# GPS_TRACKER_MINI.net
KiCad netlist of a schematic drawn in EAGLE
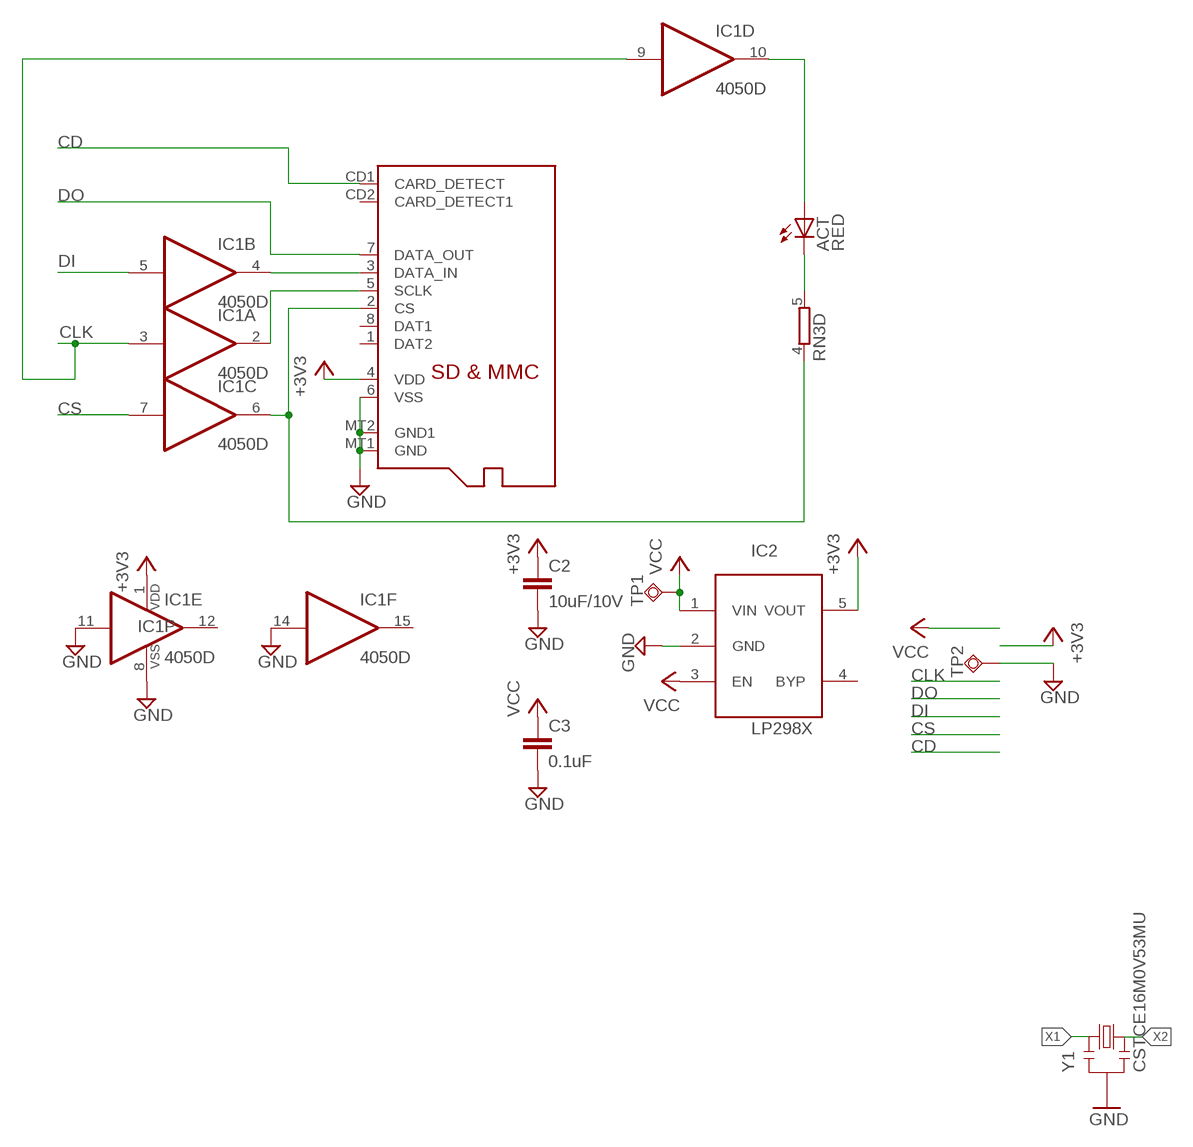
[diagram p0: schematic, sheet 1, part 1 of 2]
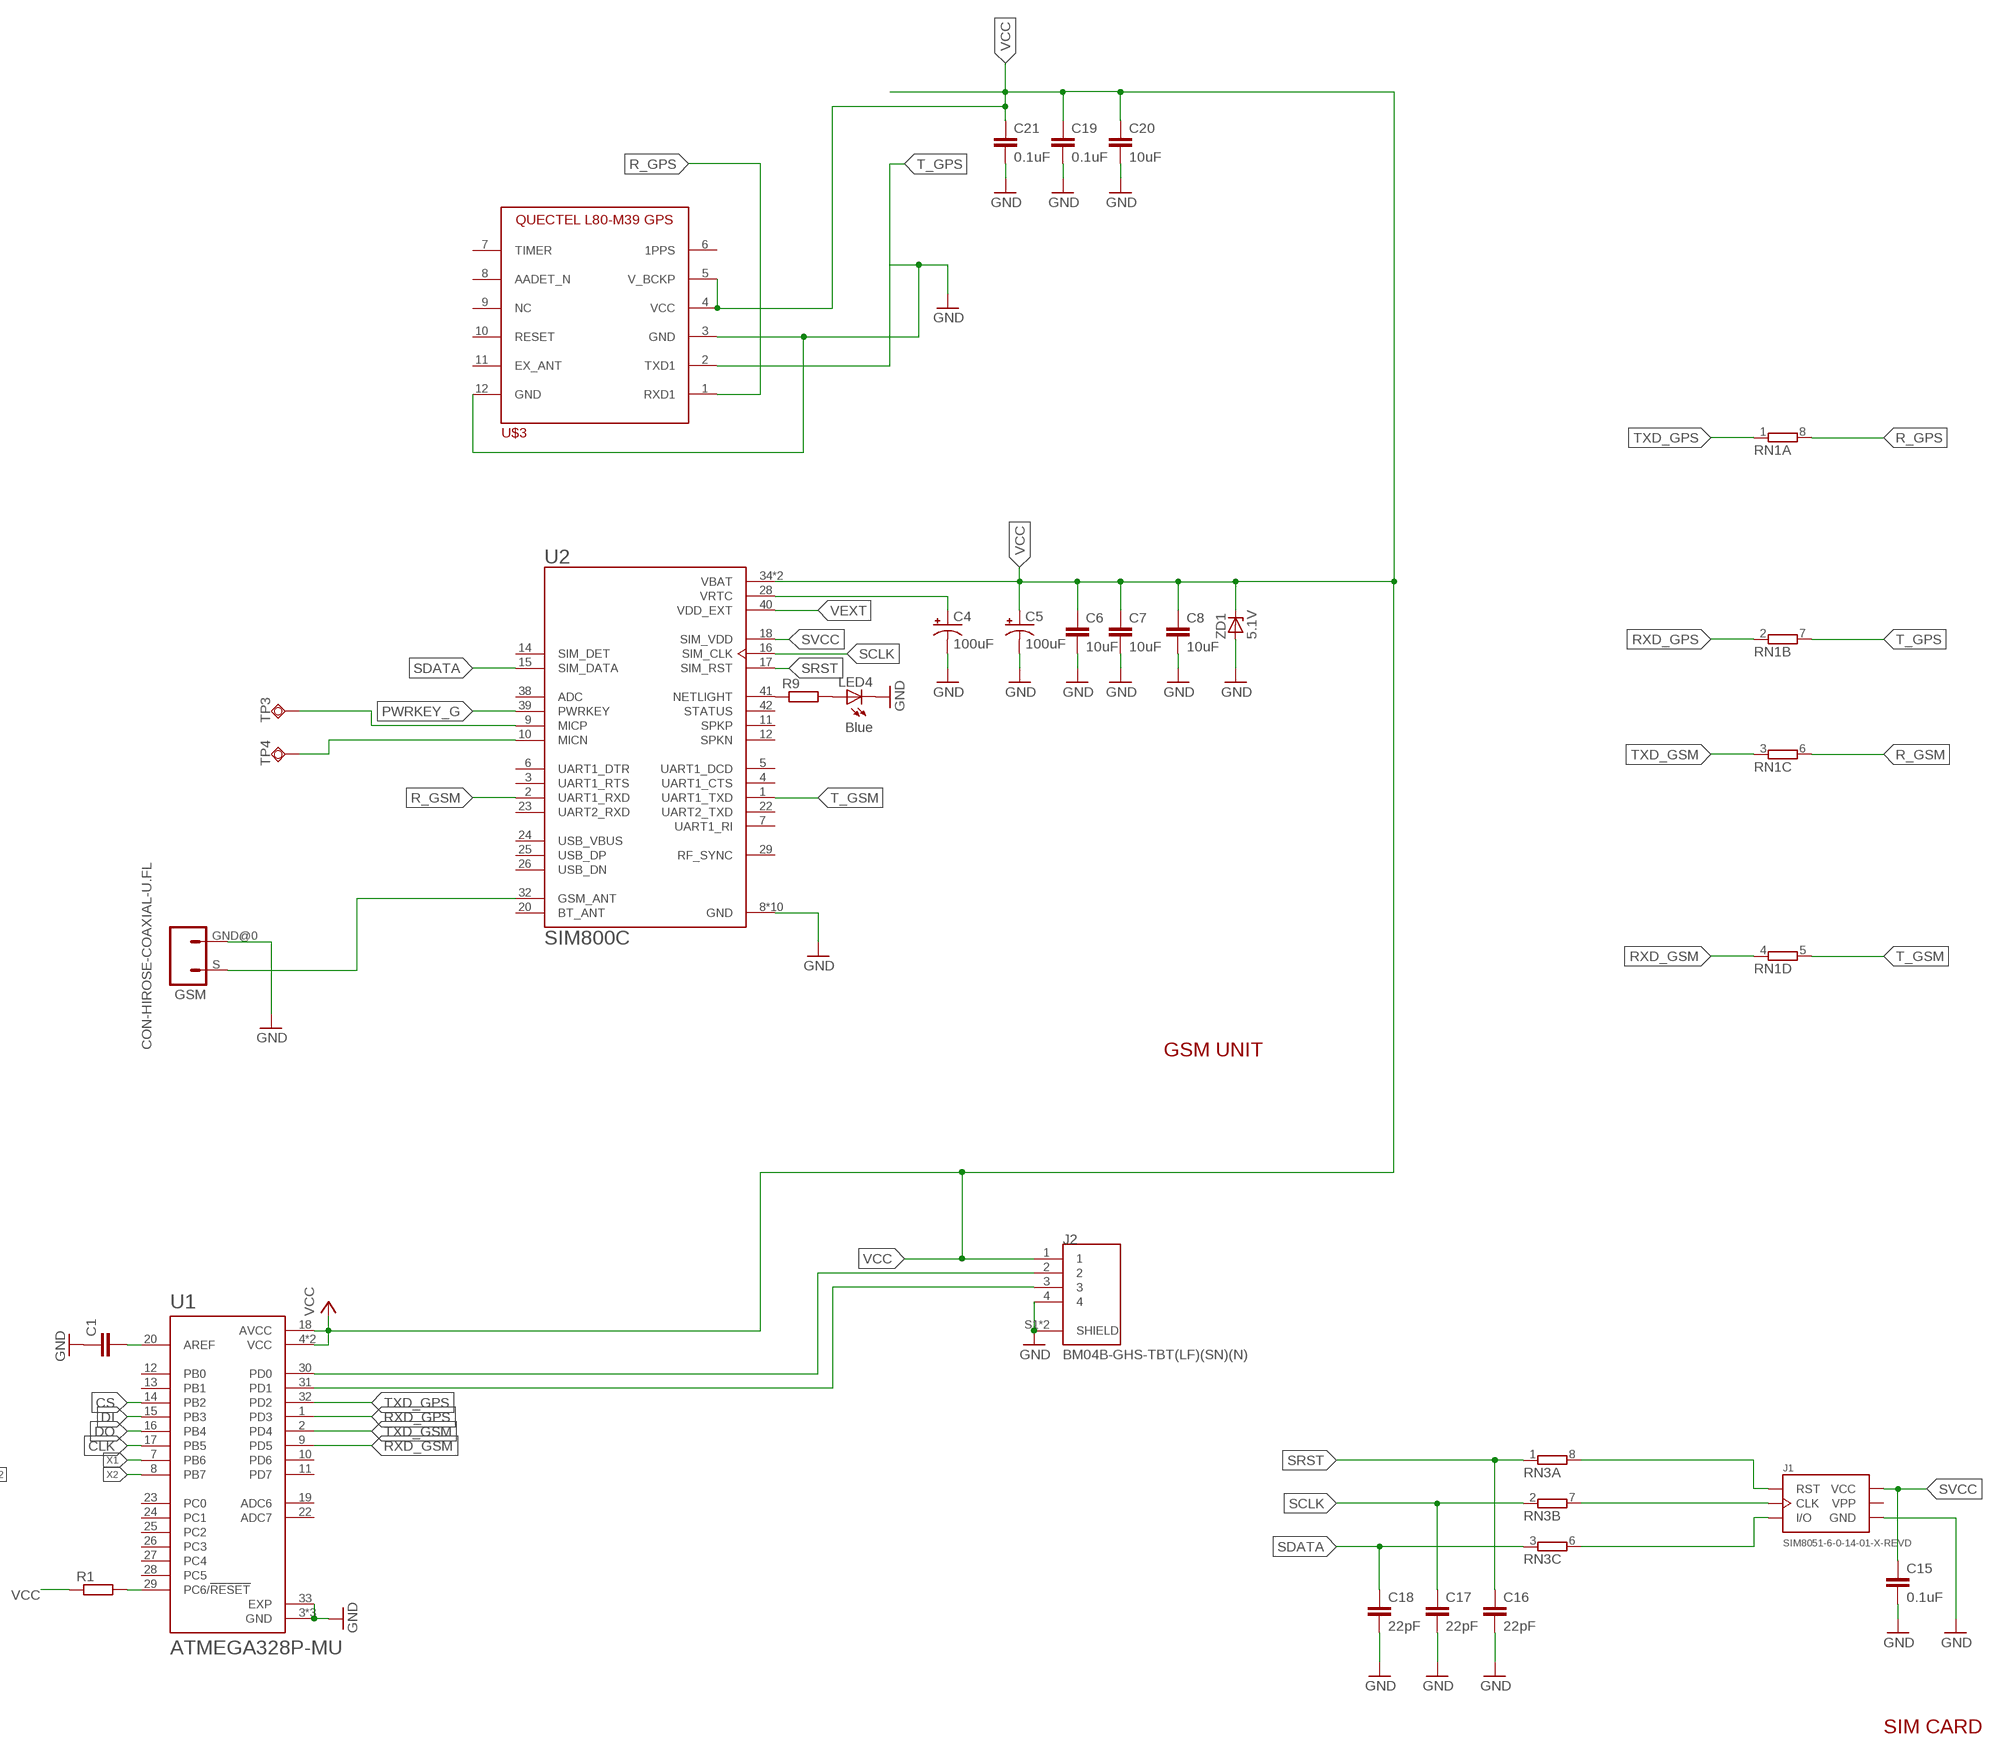
[diagram p1: schematic, sheet 1, part 2 of 2]

(export (version "E")
  (design (tool "Eeschema 10.0.6"))
  (components
    (comp (ref "ACT")
      (value "RED")
      (footprint "eagle-import:CHIP-LED0805")
      (libsource (lib "eagle-import") (part "LEDCHIP-LED0805"))
    )
    (comp (ref "C1")
      (value "C-EUC0603K")
      (footprint "eagle-import:C0603K")
      (libsource (lib "eagle-import") (part "C-EUC0603K"))
    )
    (comp (ref "C2")
      (value "10uF/10V")
      (footprint "eagle-import:C0603")
      (libsource (lib "eagle-import") (part "C-EUC0603"))
    )
    (comp (ref "C3")
      (value "0.1uF")
      (footprint "eagle-import:C0603")
      (libsource (lib "eagle-import") (part "C-EUC0603"))
    )
    (comp (ref "C4")
      (value "100uF")
      (footprint "eagle-import:B_3528-21R")
      (libsource (lib "eagle-import") (part "CPOL-USB/3528-21R"))
    )
    (comp (ref "C5")
      (value "100uF")
      (footprint "eagle-import:B_3528-21R")
      (libsource (lib "eagle-import") (part "CPOL-USB/3528-21R"))
    )
    (comp (ref "C6")
      (value "10uF")
      (footprint "eagle-import:C0603")
      (libsource (lib "eagle-import") (part "C-EUC0603"))
    )
    (comp (ref "C7")
      (value "10uF")
      (footprint "eagle-import:C0603")
      (libsource (lib "eagle-import") (part "C-EUC0603"))
    )
    (comp (ref "C8")
      (value "10uF")
      (footprint "eagle-import:C0603")
      (libsource (lib "eagle-import") (part "C-EUC0603"))
    )
    (comp (ref "C15")
      (value "0.1uF")
      (footprint "eagle-import:C0603")
      (libsource (lib "eagle-import") (part "C-EUC0603"))
    )
    (comp (ref "C16")
      (value "22pF")
      (footprint "eagle-import:C0603")
      (libsource (lib "eagle-import") (part "C-EUC0603"))
    )
    (comp (ref "C17")
      (value "22pF")
      (footprint "eagle-import:C0603")
      (libsource (lib "eagle-import") (part "C-EUC0603"))
    )
    (comp (ref "C18")
      (value "22pF")
      (footprint "eagle-import:C0603")
      (libsource (lib "eagle-import") (part "C-EUC0603"))
    )
    (comp (ref "C19")
      (value "0.1uF")
      (footprint "eagle-import:C0603")
      (libsource (lib "eagle-import") (part "C-EUC0603"))
    )
    (comp (ref "C20")
      (value "10uF")
      (footprint "eagle-import:C0603")
      (libsource (lib "eagle-import") (part "C-EUC0603"))
    )
    (comp (ref "C21")
      (value "0.1uF")
      (footprint "eagle-import:C0603")
      (libsource (lib "eagle-import") (part "C-EUC0603"))
    )
    (comp (ref "GSM")
      (value "CON-HIROSE-COAXIAL-U.FL")
      (footprint "eagle-import:CON-U.FL")
      (libsource (lib "eagle-import") (part "CON-HIROSE-COAXIAL-U.FL"))
    )
    (comp (ref "IC1")
      (value "4050D")
      (footprint "eagle-import:SO16")
      (libsource (lib "eagle-import") (part "4050D"))
    )
    (comp (ref "IC2")
      (value "LP298XS")
      (footprint "eagle-import:SOT23-5L")
      (libsource (lib "eagle-import") (part "LP298XS"))
    )
    (comp (ref "J1")
      (value "SIM8051-6-0-14-01-X-REVD")
      (footprint "eagle-import:GCT_SIM8051-6-0-14-01-X-REVD")
      (fields (field (name "MF") "Global Connector Technology") (field (name "MP") "SIM8051-6-0-14-01-A"))
      (libsource (lib "eagle-import") (part "SIM8051-6-0-14-01-X-REVD"))
    )
    (comp (ref "J2")
      (value "BM04B-GHS-TBT(LF)(SN)(N)")
      (footprint "eagle-import:JST_BM04B-GHS-TBT(LF)(SN)(N)")
      (fields (field (name "MF") "JST Sales"))
      (libsource (lib "eagle-import") (part "BM04B-GHS-TBT(LF)(SN)(N)"))
    )
    (comp (ref "LED4")
      (value "Blue")
      (footprint "eagle-import:CHIP-LED0805")
      (libsource (lib "eagle-import") (part "LEDCHIP-LED0805"))
    )
    (comp (ref "R1")
      (value "R-EU_R0603")
      (footprint "eagle-import:R0603")
      (libsource (lib "eagle-import") (part "R-EU_R0603"))
    )
    (comp (ref "R9")
      (value "R-EU_R0603")
      (footprint "eagle-import:R0603")
      (libsource (lib "eagle-import") (part "R-EU_R0603"))
    )
    (comp (ref "RN1")
      (value "4R-N0603-ARC")
      (footprint "eagle-import:0603-ARC")
      (libsource (lib "eagle-import") (part "4R-N0603-ARC"))
    )
    (comp (ref "RN3")
      (value "4R-N0603-ARC")
      (footprint "eagle-import:0603-ARC")
      (libsource (lib "eagle-import") (part "4R-N0603-ARC"))
    )
    (comp (ref "TP1")
      (value "TPSQTP20R")
      (footprint "eagle-import:TP20R")
      (libsource (lib "eagle-import") (part "TPSQTP20R"))
    )
    (comp (ref "TP2")
      (value "TPSQTP20R")
      (footprint "eagle-import:TP20R")
      (libsource (lib "eagle-import") (part "TPSQTP20R"))
    )
    (comp (ref "TP3")
      (value "TPSQTP14R")
      (footprint "eagle-import:TP14R")
      (libsource (lib "eagle-import") (part "TPSQTP14R"))
    )
    (comp (ref "TP4")
      (value "TPSQTP14R")
      (footprint "eagle-import:TP14R")
      (libsource (lib "eagle-import") (part "TPSQTP14R"))
    )
    (comp (ref "U$3")
      (value "L80_GNSS_MODULE")
      (footprint "eagle-import:L80_PACKAGE")
      (libsource (lib "eagle-import") (part "L80_GNSS_MODULE"))
    )
    (comp (ref "U1")
      (value "ATMEGA328P-MU")
      (footprint "eagle-import:QFN50P500X500X100-33N")
      (fields (field (name "MF") "Microchip"))
      (libsource (lib "eagle-import") (part "ATMEGA328P-MU"))
    )
    (comp (ref "U2")
      (value "SIM800C")
      (footprint "eagle-import:LCC110P1570X1760X250-42N")
      (fields (field (name "MF") "Simcom"))
      (libsource (lib "eagle-import") (part "SIM800C"))
    )
    (comp (ref "X1")
      (value "MICROSD")
      (footprint "eagle-import:MICROSD")
      (libsource (lib "eagle-import") (part "MICROSD"))
    )
    (comp (ref "Y1")
      (value "CSTCE16M0V53MU")
      (footprint "eagle-import:CSTCE16M0V53")
      (fields (field (name "MF") "Murata Electronics") (field (name "MP") "CSTCE16M0V53"))
      (libsource (lib "eagle-import") (part "CSTCE16M0V53MU"))
    )
    (comp (ref "ZD1")
      (value "5.1V")
      (footprint "eagle-import:SOD123")
      (libsource (lib "eagle-import") (part "ZD-SOD123"))
    )
  )
  (nets
    (net (code "1") (name "+3V3") (class "Default")
      (node (ref "C2") (pin "1") (pinfunction "1_1") (pintype "passive"))
      (node (ref "IC1") (pin "1") (pinfunction "VDD_1") (pintype "power_in"))
      (node (ref "IC2") (pin "5") (pinfunction "VOUT_5") (pintype "bidirectional"))
      (node (ref "X1") (pin "4") (pinfunction "VDD_4") (pintype "power_in"))
    )
    (net (code "2") (name "/CD") (class "Default")
      (node (ref "X1") (pin "CD1") (pinfunction "CARD_DETECT_CD1") (pintype "passive"))
    )
    (net (code "3") (name "/VPP") (class "Default")
      (node (ref "J1") (pin "C6") (pinfunction "VPP_C6") (pintype "power_in"))
    )
    (net (code "4") (name "CLK") (class "Default")
      (node (ref "IC1") (pin "3") (pinfunction "I_3") (pintype "input"))
      (node (ref "IC1") (pin "9") (pinfunction "I_9") (pintype "input"))
      (node (ref "U1") (pin "17") (pinfunction "PB5_17") (pintype "bidirectional"))
    )
    (net (code "5") (name "CS") (class "Default")
      (node (ref "IC1") (pin "7") (pinfunction "I_7") (pintype "input"))
      (node (ref "U1") (pin "14") (pinfunction "PB2_14") (pintype "bidirectional"))
    )
    (net (code "6") (name "DI") (class "Default")
      (node (ref "IC1") (pin "5") (pinfunction "I_5") (pintype "input"))
      (node (ref "U1") (pin "15") (pinfunction "PB3_15") (pintype "bidirectional"))
    )
    (net (code "7") (name "DO") (class "Default")
      (node (ref "U1") (pin "16") (pinfunction "PB4_16") (pintype "bidirectional"))
      (node (ref "X1") (pin "7") (pinfunction "DATA_OUT_7") (pintype "output"))
    )
    (net (code "8") (name "GND") (class "Default")
      (node (ref "C1") (pin "1") (pinfunction "1_1") (pintype "passive"))
      (node (ref "C15") (pin "2") (pinfunction "2_2") (pintype "passive"))
      (node (ref "C16") (pin "2") (pinfunction "2_2") (pintype "passive"))
      (node (ref "C17") (pin "2") (pinfunction "2_2") (pintype "passive"))
      (node (ref "C18") (pin "2") (pinfunction "2_2") (pintype "passive"))
      (node (ref "C19") (pin "2") (pinfunction "2_2") (pintype "passive"))
      (node (ref "C2") (pin "2") (pinfunction "2_2") (pintype "passive"))
      (node (ref "C20") (pin "2") (pinfunction "2_2") (pintype "passive"))
      (node (ref "C21") (pin "2") (pinfunction "2_2") (pintype "passive"))
      (node (ref "C3") (pin "2") (pinfunction "2_2") (pintype "passive"))
      (node (ref "C4") (pin "-") (pinfunction "-_-") (pintype "passive"))
      (node (ref "C5") (pin "-") (pinfunction "-_-") (pintype "passive"))
      (node (ref "C6") (pin "2") (pinfunction "2_2") (pintype "passive"))
      (node (ref "C7") (pin "2") (pinfunction "2_2") (pintype "passive"))
      (node (ref "C8") (pin "2") (pinfunction "2_2") (pintype "passive"))
      (node (ref "GSM") (pin "GND@0") (pinfunction "2_GND@0") (pintype "passive"))
      (node (ref "IC1") (pin "11") (pinfunction "I_11") (pintype "input"))
      (node (ref "IC1") (pin "14") (pinfunction "I_14") (pintype "input"))
      (node (ref "IC1") (pin "8") (pinfunction "VSS_8") (pintype "power_in"))
      (node (ref "IC2") (pin "2") (pinfunction "GND_2") (pintype "bidirectional"))
      (node (ref "J1") (pin "C5") (pinfunction "GND_C5") (pintype "power_in"))
      (node (ref "J2") (pin "4") (pinfunction "4_4") (pintype "passive"))
      (node (ref "J2") (pin "S1") (pinfunction "SHIELD_S1") (pintype "passive"))
      (node (ref "J2") (pin "S2") (pinfunction "SHIELD_S2") (pintype "passive"))
      (node (ref "LED4") (pin "C") (pinfunction "C_C") (pintype "passive"))
      (node (ref "TP2") (pin "TP") (pinfunction "TP_TP") (pintype "input"))
      (node (ref "U$3") (pin "12") (pinfunction "GND_12") (pintype "bidirectional"))
      (node (ref "U$3") (pin "3") (pinfunction "GND_3") (pintype "bidirectional"))
      (node (ref "U1") (pin "21") (pinfunction "GND_21") (pintype "power_in"))
      (node (ref "U1") (pin "3") (pinfunction "GND_3") (pintype "power_in"))
      (node (ref "U1") (pin "33") (pinfunction "EXP_33") (pintype "power_in"))
      (node (ref "U1") (pin "5") (pinfunction "GND_5") (pintype "power_in"))
      (node (ref "U2") (pin "13") (pinfunction "GND_13") (pintype "power_in"))
      (node (ref "U2") (pin "19") (pinfunction "GND_19") (pintype "power_in"))
      (node (ref "U2") (pin "21") (pinfunction "GND_21") (pintype "power_in"))
      (node (ref "U2") (pin "27") (pinfunction "GND_27") (pintype "power_in"))
      (node (ref "U2") (pin "30") (pinfunction "GND_30") (pintype "power_in"))
      (node (ref "U2") (pin "31") (pinfunction "GND_31") (pintype "power_in"))
      (node (ref "U2") (pin "33") (pinfunction "GND_33") (pintype "power_in"))
      (node (ref "U2") (pin "36") (pinfunction "GND_36") (pintype "power_in"))
      (node (ref "U2") (pin "37") (pinfunction "GND_37") (pintype "power_in"))
      (node (ref "U2") (pin "8") (pinfunction "GND_8") (pintype "power_in"))
      (node (ref "X1") (pin "6") (pinfunction "VSS_6") (pintype "power_in"))
      (node (ref "X1") (pin "MT1") (pinfunction "GND_MT1") (pintype "power_in"))
      (node (ref "X1") (pin "MT2") (pinfunction "GND1_MT2") (pintype "power_in"))
      (node (ref "Y1") (pin "2") (pinfunction "2_2") (pintype "passive"))
      (node (ref "ZD1") (pin "A") (pinfunction "A_A") (pintype "passive"))
    )
    (net (code "9") (name "Net-(GSM-1)") (class "Default")
      (node (ref "GSM") (pin "S") (pinfunction "1_S") (pintype "passive"))
      (node (ref "U2") (pin "32") (pinfunction "GSM_ANT_32") (pintype "bidirectional"))
    )
    (net (code "10") (name "Net-(IC1A-O)") (class "Default")
      (node (ref "IC1") (pin "2") (pinfunction "O_2") (pintype "output"))
      (node (ref "X1") (pin "5") (pinfunction "SCLK_5") (pintype "input"))
    )
    (net (code "11") (name "Net-(IC1B-O)") (class "Default")
      (node (ref "IC1") (pin "4") (pinfunction "O_4") (pintype "output"))
      (node (ref "X1") (pin "3") (pinfunction "DATA_IN_3") (pintype "input"))
    )
    (net (code "12") (name "Net-(IC1C-O)") (class "Default")
      (node (ref "IC1") (pin "6") (pinfunction "O_6") (pintype "output"))
      (node (ref "RN3") (pin "4") (pinfunction "1_4") (pintype "passive"))
      (node (ref "X1") (pin "2") (pinfunction "CS_2") (pintype "input"))
    )
    (net (code "13") (name "Net-(IC1D-O)") (class "Default")
      (node (ref "ACT") (pin "A") (pinfunction "A_A") (pintype "passive"))
      (node (ref "IC1") (pin "10") (pinfunction "O_10") (pintype "output"))
    )
    (net (code "14") (name "Net-(J1-CLK)") (class "Default")
      (node (ref "J1") (pin "C3") (pinfunction "CLK_C3") (pintype "input"))
      (node (ref "RN3") (pin "7") (pinfunction "2_7") (pintype "passive"))
    )
    (net (code "15") (name "Net-(J1-I{slash}O)") (class "Default")
      (node (ref "J1") (pin "C7") (pinfunction "I/O_C7") (pintype "bidirectional"))
      (node (ref "RN3") (pin "6") (pinfunction "2_6") (pintype "passive"))
    )
    (net (code "16") (name "Net-(J1-RST)") (class "Default")
      (node (ref "J1") (pin "C2") (pinfunction "RST_C2") (pintype "input"))
      (node (ref "RN3") (pin "8") (pinfunction "2_8") (pintype "passive"))
    )
    (net (code "17") (name "Net-(LED4-PadA)") (class "Default")
      (node (ref "LED4") (pin "A") (pinfunction "A_A") (pintype "passive"))
      (node (ref "R9") (pin "2") (pinfunction "2_2") (pintype "passive"))
    )
    (net (code "18") (name "Net-(RN3D-2)") (class "Default")
      (node (ref "ACT") (pin "C") (pinfunction "C_C") (pintype "passive"))
      (node (ref "RN3") (pin "5") (pinfunction "2_5") (pintype "passive"))
    )
    (net (code "19") (name "Net-(U1-AREF)") (class "Default")
      (node (ref "C1") (pin "2") (pinfunction "2_2") (pintype "passive"))
      (node (ref "U1") (pin "20") (pinfunction "AREF_20") (pintype "input"))
    )
    (net (code "20") (name "Net-(U1-PC6{slash}~{RESET})") (class "Default")
      (node (ref "R1") (pin "2") (pinfunction "2_2") (pintype "passive"))
      (node (ref "U1") (pin "29") (pinfunction "PC6/~{RESET}_29") (pintype "bidirectional"))
    )
    (net (code "21") (name "Net-(U1-PD0)") (class "Default")
      (node (ref "J2") (pin "2") (pinfunction "2_2") (pintype "passive"))
      (node (ref "U1") (pin "30") (pinfunction "PD0_30") (pintype "bidirectional"))
    )
    (net (code "22") (name "Net-(U1-PD1)") (class "Default")
      (node (ref "J2") (pin "3") (pinfunction "3_3") (pintype "passive"))
      (node (ref "U1") (pin "31") (pinfunction "PD1_31") (pintype "bidirectional"))
    )
    (net (code "23") (name "Net-(U2-MICN)") (class "Default")
      (node (ref "TP4") (pin "TP") (pinfunction "TP_TP") (pintype "input"))
      (node (ref "U2") (pin "10") (pinfunction "MICN_10") (pintype "input"))
    )
    (net (code "24") (name "Net-(U2-MICP)") (class "Default")
      (node (ref "TP3") (pin "TP") (pinfunction "TP_TP") (pintype "input"))
      (node (ref "U2") (pin "9") (pinfunction "MICP_9") (pintype "input"))
    )
    (net (code "25") (name "Net-(U2-NETLIGHT)") (class "Default")
      (node (ref "R9") (pin "1") (pinfunction "1_1") (pintype "passive"))
      (node (ref "U2") (pin "41") (pinfunction "NETLIGHT_41") (pintype "output"))
    )
    (net (code "26") (name "Net-(U2-VRTC)") (class "Default")
      (node (ref "C4") (pin "+") (pinfunction "+_+") (pintype "passive"))
      (node (ref "U2") (pin "28") (pinfunction "VRTC_28") (pintype "power_in"))
    )
    (net (code "27") (name "PWRKEY_G") (class "Default")
      (node (ref "U2") (pin "39") (pinfunction "PWRKEY_39") (pintype "input"))
    )
    (net (code "28") (name "RXD_GPS") (class "Default")
      (node (ref "RN1") (pin "2") (pinfunction "1_2") (pintype "passive"))
      (node (ref "U1") (pin "1") (pinfunction "PD3_1") (pintype "bidirectional"))
    )
    (net (code "29") (name "RXD_GSM") (class "Default")
      (node (ref "RN1") (pin "4") (pinfunction "1_4") (pintype "passive"))
      (node (ref "U1") (pin "9") (pinfunction "PD5_9") (pintype "bidirectional"))
    )
    (net (code "30") (name "R_GPS") (class "Default")
      (node (ref "RN1") (pin "8") (pinfunction "2_8") (pintype "passive"))
      (node (ref "U$3") (pin "1") (pinfunction "RXD1_1") (pintype "bidirectional"))
    )
    (net (code "31") (name "R_GSM") (class "Default")
      (node (ref "RN1") (pin "6") (pinfunction "2_6") (pintype "passive"))
      (node (ref "U2") (pin "2") (pinfunction "UART1_RXD_2") (pintype "input"))
    )
    (net (code "32") (name "SCLK") (class "Default")
      (node (ref "C17") (pin "1") (pinfunction "1_1") (pintype "passive"))
      (node (ref "RN3") (pin "2") (pinfunction "1_2") (pintype "passive"))
      (node (ref "U2") (pin "16") (pinfunction "SIM_CLK_16") (pintype "output"))
    )
    (net (code "33") (name "SDATA") (class "Default")
      (node (ref "C18") (pin "1") (pinfunction "1_1") (pintype "passive"))
      (node (ref "RN3") (pin "3") (pinfunction "1_3") (pintype "passive"))
      (node (ref "U2") (pin "15") (pinfunction "SIM_DATA_15") (pintype "bidirectional"))
    )
    (net (code "34") (name "SRST") (class "Default")
      (node (ref "C16") (pin "1") (pinfunction "1_1") (pintype "passive"))
      (node (ref "RN3") (pin "1") (pinfunction "1_1") (pintype "passive"))
      (node (ref "U2") (pin "17") (pinfunction "SIM_RST_17") (pintype "output"))
    )
    (net (code "35") (name "SVCC") (class "Default")
      (node (ref "C15") (pin "1") (pinfunction "1_1") (pintype "passive"))
      (node (ref "J1") (pin "C1") (pinfunction "VCC_C1") (pintype "power_in"))
      (node (ref "U2") (pin "18") (pinfunction "SIM_VDD_18") (pintype "output"))
    )
    (net (code "36") (name "TXD_GPS") (class "Default")
      (node (ref "RN1") (pin "1") (pinfunction "1_1") (pintype "passive"))
      (node (ref "U1") (pin "32") (pinfunction "PD2_32") (pintype "bidirectional"))
    )
    (net (code "37") (name "TXD_GSM") (class "Default")
      (node (ref "RN1") (pin "3") (pinfunction "1_3") (pintype "passive"))
      (node (ref "U1") (pin "2") (pinfunction "PD4_2") (pintype "bidirectional"))
    )
    (net (code "38") (name "T_GPS") (class "Default")
      (node (ref "RN1") (pin "7") (pinfunction "2_7") (pintype "passive"))
      (node (ref "U$3") (pin "2") (pinfunction "TXD1_2") (pintype "bidirectional"))
    )
    (net (code "39") (name "T_GSM") (class "Default")
      (node (ref "RN1") (pin "5") (pinfunction "2_5") (pintype "passive"))
      (node (ref "U2") (pin "1") (pinfunction "UART1_TXD_1") (pintype "output"))
    )
    (net (code "40") (name "VCC") (class "Default")
      (node (ref "C19") (pin "1") (pinfunction "1_1") (pintype "passive"))
      (node (ref "C20") (pin "1") (pinfunction "1_1") (pintype "passive"))
      (node (ref "C21") (pin "1") (pinfunction "1_1") (pintype "passive"))
      (node (ref "C3") (pin "1") (pinfunction "1_1") (pintype "passive"))
      (node (ref "C5") (pin "+") (pinfunction "+_+") (pintype "passive"))
      (node (ref "C6") (pin "1") (pinfunction "1_1") (pintype "passive"))
      (node (ref "C7") (pin "1") (pinfunction "1_1") (pintype "passive"))
      (node (ref "C8") (pin "1") (pinfunction "1_1") (pintype "passive"))
      (node (ref "IC2") (pin "1") (pinfunction "VIN_1") (pintype "bidirectional"))
      (node (ref "IC2") (pin "3") (pinfunction "EN_3") (pintype "bidirectional"))
      (node (ref "J2") (pin "1") (pinfunction "1_1") (pintype "passive"))
      (node (ref "R1") (pin "1") (pinfunction "1_1") (pintype "passive"))
      (node (ref "TP1") (pin "TP") (pinfunction "TP_TP") (pintype "input"))
      (node (ref "U$3") (pin "4") (pinfunction "VCC_4") (pintype "bidirectional"))
      (node (ref "U$3") (pin "5") (pinfunction "V_BCKP_5") (pintype "bidirectional"))
      (node (ref "U1") (pin "18") (pinfunction "AVCC_18") (pintype "power_in"))
      (node (ref "U1") (pin "4") (pinfunction "VCC_4") (pintype "power_in"))
      (node (ref "U1") (pin "6") (pinfunction "VCC_6") (pintype "power_in"))
      (node (ref "U2") (pin "34") (pinfunction "VBAT_34") (pintype "power_in"))
      (node (ref "U2") (pin "35") (pinfunction "VBAT_35") (pintype "power_in"))
      (node (ref "ZD1") (pin "C") (pinfunction "C_C") (pintype "passive"))
    )
    (net (code "41") (name "VEXT") (class "Default")
      (node (ref "U2") (pin "40") (pinfunction "VDD_EXT_40") (pintype "power_in"))
    )
    (net (code "42") (name "X1") (class "Default")
      (node (ref "U1") (pin "7") (pinfunction "PB6_7") (pintype "bidirectional"))
      (node (ref "Y1") (pin "1") (pinfunction "1_1") (pintype "passive"))
    )
    (net (code "43") (name "X2") (class "Default")
      (node (ref "U1") (pin "8") (pinfunction "PB7_8") (pintype "bidirectional"))
      (node (ref "Y1") (pin "3") (pinfunction "3_3") (pintype "passive"))
    )
    (net (code "44") (name "unconnected-(IC1E-O-Pad12)") (class "Default")
      (node (ref "IC1") (pin "12") (pinfunction "O_12") (pintype "output"))
    )
    (net (code "45") (name "unconnected-(IC1F-O-Pad15)") (class "Default")
      (node (ref "IC1") (pin "15") (pinfunction "O_15") (pintype "output"))
    )
    (net (code "46") (name "unconnected-(IC2-BYP-Pad4)") (class "Default")
      (node (ref "IC2") (pin "4") (pinfunction "BYP_4") (pintype "bidirectional"))
    )
    (net (code "47") (name "unconnected-(U$3-1PPS-Pad6)") (class "Default")
      (node (ref "U$3") (pin "6") (pinfunction "1PPS_6") (pintype "bidirectional"))
    )
    (net (code "48") (name "unconnected-(U$3-AADET_N-Pad8)") (class "Default")
      (node (ref "U$3") (pin "8") (pinfunction "AADET_N_8") (pintype "bidirectional"))
    )
    (net (code "49") (name "unconnected-(U$3-EX_ANT-Pad11)") (class "Default")
      (node (ref "U$3") (pin "11") (pinfunction "EX_ANT_11") (pintype "bidirectional"))
    )
    (net (code "50") (name "unconnected-(U$3-NC-Pad9)") (class "Default")
      (node (ref "U$3") (pin "9") (pinfunction "NC_9") (pintype "bidirectional"))
    )
    (net (code "51") (name "unconnected-(U$3-RESET-Pad10)") (class "Default")
      (node (ref "U$3") (pin "10") (pinfunction "RESET_10") (pintype "bidirectional"))
    )
    (net (code "52") (name "unconnected-(U$3-TIMER-Pad7)") (class "Default")
      (node (ref "U$3") (pin "7") (pinfunction "TIMER_7") (pintype "bidirectional"))
    )
    (net (code "53") (name "unconnected-(U1-ADC6-Pad19)") (class "Default")
      (node (ref "U1") (pin "19") (pinfunction "ADC6_19") (pintype "bidirectional"))
    )
    (net (code "54") (name "unconnected-(U1-ADC7-Pad22)") (class "Default")
      (node (ref "U1") (pin "22") (pinfunction "ADC7_22") (pintype "bidirectional"))
    )
    (net (code "55") (name "unconnected-(U1-PB0-Pad12)") (class "Default")
      (node (ref "U1") (pin "12") (pinfunction "PB0_12") (pintype "bidirectional"))
    )
    (net (code "56") (name "unconnected-(U1-PB1-Pad13)") (class "Default")
      (node (ref "U1") (pin "13") (pinfunction "PB1_13") (pintype "bidirectional"))
    )
    (net (code "57") (name "unconnected-(U1-PC0-Pad23)") (class "Default")
      (node (ref "U1") (pin "23") (pinfunction "PC0_23") (pintype "bidirectional"))
    )
    (net (code "58") (name "unconnected-(U1-PC1-Pad24)") (class "Default")
      (node (ref "U1") (pin "24") (pinfunction "PC1_24") (pintype "bidirectional"))
    )
    (net (code "59") (name "unconnected-(U1-PC2-Pad25)") (class "Default")
      (node (ref "U1") (pin "25") (pinfunction "PC2_25") (pintype "bidirectional"))
    )
    (net (code "60") (name "unconnected-(U1-PC3-Pad26)") (class "Default")
      (node (ref "U1") (pin "26") (pinfunction "PC3_26") (pintype "bidirectional"))
    )
    (net (code "61") (name "unconnected-(U1-PC4-Pad27)") (class "Default")
      (node (ref "U1") (pin "27") (pinfunction "PC4_27") (pintype "bidirectional"))
    )
    (net (code "62") (name "unconnected-(U1-PC5-Pad28)") (class "Default")
      (node (ref "U1") (pin "28") (pinfunction "PC5_28") (pintype "bidirectional"))
    )
    (net (code "63") (name "unconnected-(U1-PD6-Pad10)") (class "Default")
      (node (ref "U1") (pin "10") (pinfunction "PD6_10") (pintype "bidirectional"))
    )
    (net (code "64") (name "unconnected-(U1-PD7-Pad11)") (class "Default")
      (node (ref "U1") (pin "11") (pinfunction "PD7_11") (pintype "bidirectional"))
    )
    (net (code "65") (name "unconnected-(U2-ADC-Pad38)") (class "Default")
      (node (ref "U2") (pin "38") (pinfunction "ADC_38") (pintype "input"))
    )
    (net (code "66") (name "unconnected-(U2-BT_ANT-Pad20)") (class "Default")
      (node (ref "U2") (pin "20") (pinfunction "BT_ANT_20") (pintype "bidirectional"))
    )
    (net (code "67") (name "unconnected-(U2-RF_SYNC-Pad29)") (class "Default")
      (node (ref "U2") (pin "29") (pinfunction "RF_SYNC_29") (pintype "output"))
    )
    (net (code "68") (name "unconnected-(U2-SIM_DET-Pad14)") (class "Default")
      (node (ref "U2") (pin "14") (pinfunction "SIM_DET_14") (pintype "input"))
    )
    (net (code "69") (name "unconnected-(U2-SPKN-Pad12)") (class "Default")
      (node (ref "U2") (pin "12") (pinfunction "SPKN_12") (pintype "output"))
    )
    (net (code "70") (name "unconnected-(U2-SPKP-Pad11)") (class "Default")
      (node (ref "U2") (pin "11") (pinfunction "SPKP_11") (pintype "output"))
    )
    (net (code "71") (name "unconnected-(U2-STATUS-Pad42)") (class "Default")
      (node (ref "U2") (pin "42") (pinfunction "STATUS_42") (pintype "output"))
    )
    (net (code "72") (name "unconnected-(U2-UART1_CTS-Pad4)") (class "Default")
      (node (ref "U2") (pin "4") (pinfunction "UART1_CTS_4") (pintype "output"))
    )
    (net (code "73") (name "unconnected-(U2-UART1_DCD-Pad5)") (class "Default")
      (node (ref "U2") (pin "5") (pinfunction "UART1_DCD_5") (pintype "output"))
    )
    (net (code "74") (name "unconnected-(U2-UART1_DTR-Pad6)") (class "Default")
      (node (ref "U2") (pin "6") (pinfunction "UART1_DTR_6") (pintype "input"))
    )
    (net (code "75") (name "unconnected-(U2-UART1_RI-Pad7)") (class "Default")
      (node (ref "U2") (pin "7") (pinfunction "UART1_RI_7") (pintype "output"))
    )
    (net (code "76") (name "unconnected-(U2-UART1_RTS-Pad3)") (class "Default")
      (node (ref "U2") (pin "3") (pinfunction "UART1_RTS_3") (pintype "input"))
    )
    (net (code "77") (name "unconnected-(U2-UART2_RXD-Pad23)") (class "Default")
      (node (ref "U2") (pin "23") (pinfunction "UART2_RXD_23") (pintype "input"))
    )
    (net (code "78") (name "unconnected-(U2-UART2_TXD-Pad22)") (class "Default")
      (node (ref "U2") (pin "22") (pinfunction "UART2_TXD_22") (pintype "output"))
    )
    (net (code "79") (name "unconnected-(U2-USB_DN-Pad26)") (class "Default")
      (node (ref "U2") (pin "26") (pinfunction "USB_DN_26") (pintype "bidirectional"))
    )
    (net (code "80") (name "unconnected-(U2-USB_DP-Pad25)") (class "Default")
      (node (ref "U2") (pin "25") (pinfunction "USB_DP_25") (pintype "bidirectional"))
    )
    (net (code "81") (name "unconnected-(U2-USB_VBUS-Pad24)") (class "Default")
      (node (ref "U2") (pin "24") (pinfunction "USB_VBUS_24") (pintype "input"))
    )
    (net (code "82") (name "unconnected-(X1-CARD_DETECT1-PadCD2)") (class "Default")
      (node (ref "X1") (pin "CD2") (pinfunction "CARD_DETECT1_CD2") (pintype "passive"))
    )
    (net (code "83") (name "unconnected-(X1-DAT1-Pad8)") (class "Default")
      (node (ref "X1") (pin "8") (pinfunction "DAT1_8") (pintype "bidirectional"))
    )
    (net (code "84") (name "unconnected-(X1-DAT2-Pad1)") (class "Default")
      (node (ref "X1") (pin "1") (pinfunction "DAT2_1") (pintype "bidirectional"))
    )
  )
)
